# B105B.net
KiCad netlist of a schematic drawn in EAGLE
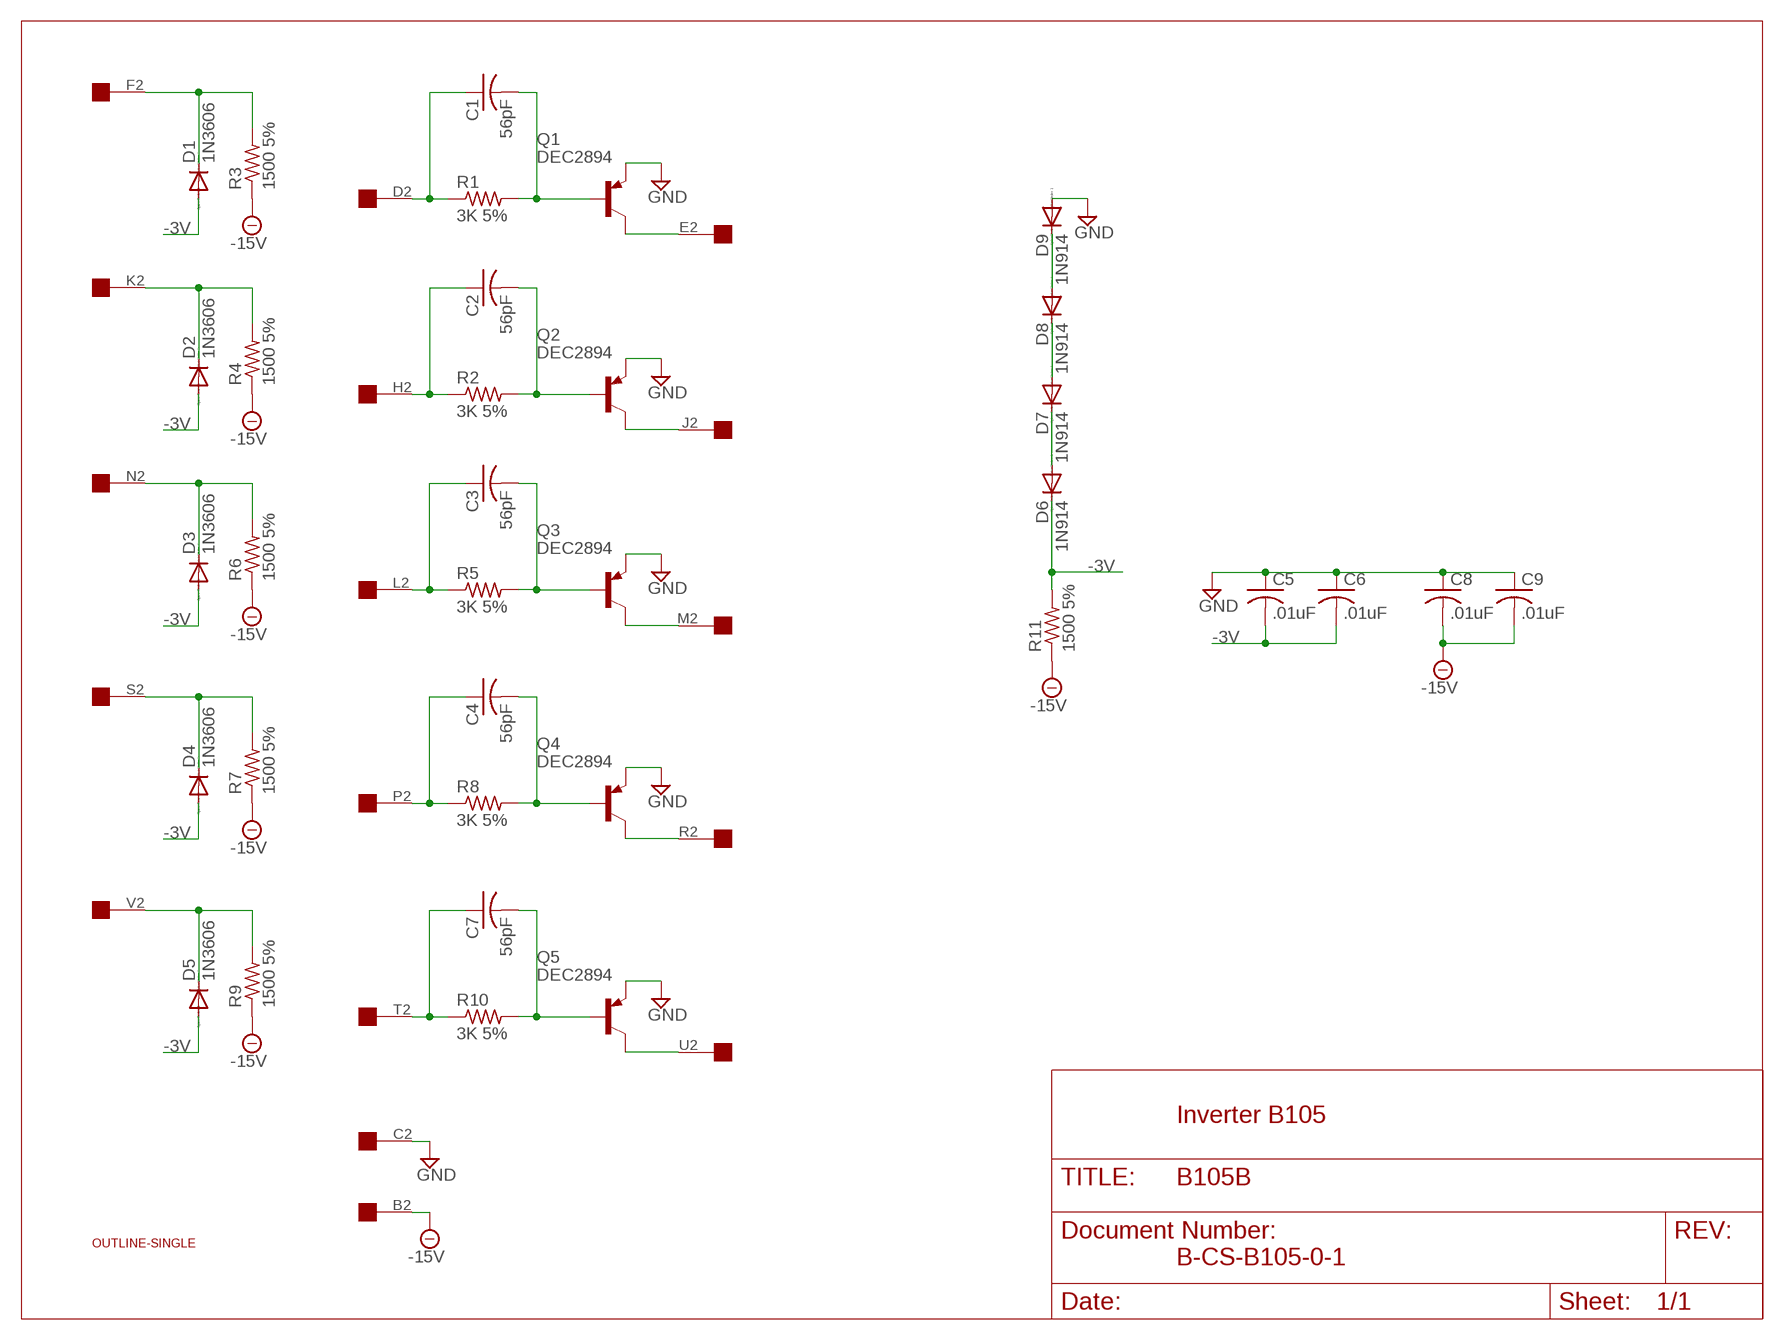
[diagram p0: schematic, sheet 1]

(export (version "E")
  (design (tool "Eeschema 10.0.6"))
  (components
    (comp (ref "C1")
      (value "56pF")
      (footprint "eagle-import:C075-032X103")
      (libsource (lib "eagle-import") (part "C-US075-032X103"))
    )
    (comp (ref "C2")
      (value "56pF")
      (footprint "eagle-import:C075-032X103")
      (libsource (lib "eagle-import") (part "C-US075-032X103"))
    )
    (comp (ref "C3")
      (value "56pF")
      (footprint "eagle-import:C075-032X103")
      (libsource (lib "eagle-import") (part "C-US075-032X103"))
    )
    (comp (ref "C4")
      (value "56pF")
      (footprint "eagle-import:C075-032X103")
      (libsource (lib "eagle-import") (part "C-US075-032X103"))
    )
    (comp (ref "C5")
      (value ".01uF")
      (footprint "eagle-import:C050-025X075")
      (libsource (lib "eagle-import") (part "C-US050-025X075"))
    )
    (comp (ref "C6")
      (value ".01uF")
      (footprint "eagle-import:C050-025X075")
      (libsource (lib "eagle-import") (part "C-US050-025X075"))
    )
    (comp (ref "C7")
      (value "56pF")
      (footprint "eagle-import:C075-032X103")
      (libsource (lib "eagle-import") (part "C-US075-032X103"))
    )
    (comp (ref "C8")
      (value ".01uF")
      (footprint "eagle-import:C050-025X075")
      (libsource (lib "eagle-import") (part "C-US050-025X075"))
    )
    (comp (ref "C9")
      (value ".01uF")
      (footprint "eagle-import:C050-025X075")
      (libsource (lib "eagle-import") (part "C-US050-025X075"))
    )
    (comp (ref "D1")
      (value "1N3606")
      (footprint "eagle-import:DO35-10")
      (libsource (lib "eagle-import") (part "1N4148DO35-10"))
    )
    (comp (ref "D2")
      (value "1N3606")
      (footprint "eagle-import:DO35-10")
      (libsource (lib "eagle-import") (part "1N4148DO35-10"))
    )
    (comp (ref "D3")
      (value "1N3606")
      (footprint "eagle-import:DO35-10")
      (libsource (lib "eagle-import") (part "1N4148DO35-10"))
    )
    (comp (ref "D4")
      (value "1N3606")
      (footprint "eagle-import:DO35-10")
      (libsource (lib "eagle-import") (part "1N4148DO35-10"))
    )
    (comp (ref "D5")
      (value "1N3606")
      (footprint "eagle-import:DO35-10")
      (libsource (lib "eagle-import") (part "1N4148DO35-10"))
    )
    (comp (ref "D6")
      (value "1N914")
      (footprint "eagle-import:DO35-10")
      (libsource (lib "eagle-import") (part "1N4148DO35-10"))
    )
    (comp (ref "D7")
      (value "1N914")
      (footprint "eagle-import:DO35-10")
      (libsource (lib "eagle-import") (part "1N4148DO35-10"))
    )
    (comp (ref "D8")
      (value "1N914")
      (footprint "eagle-import:DO35-10")
      (libsource (lib "eagle-import") (part "1N4148DO35-10"))
    )
    (comp (ref "D9")
      (value "1N914")
      (footprint "eagle-import:DO35-10")
      (libsource (lib "eagle-import") (part "1N4148DO35-10"))
    )
    (comp (ref "Q1")
      (value "DEC2894")
      (footprint "eagle-import:TO39")
      (libsource (lib "eagle-import") (part "2N2904"))
    )
    (comp (ref "Q2")
      (value "DEC2894")
      (footprint "eagle-import:TO39")
      (libsource (lib "eagle-import") (part "2N2904"))
    )
    (comp (ref "Q3")
      (value "DEC2894")
      (footprint "eagle-import:TO39")
      (libsource (lib "eagle-import") (part "2N2904"))
    )
    (comp (ref "Q4")
      (value "DEC2894")
      (footprint "eagle-import:TO39")
      (libsource (lib "eagle-import") (part "2N2904"))
    )
    (comp (ref "Q5")
      (value "DEC2894")
      (footprint "eagle-import:TO39")
      (libsource (lib "eagle-import") (part "2N2904"))
    )
    (comp (ref "R1")
      (value "3K 5%")
      (footprint "eagle-import:0207_10")
      (libsource (lib "eagle-import") (part "R-US_0207/10"))
    )
    (comp (ref "R2")
      (value "3K 5%")
      (footprint "eagle-import:0207_10")
      (libsource (lib "eagle-import") (part "R-US_0207/10"))
    )
    (comp (ref "R3")
      (value "1500 5%")
      (footprint "eagle-import:0207_10")
      (libsource (lib "eagle-import") (part "R-US_0207/10"))
    )
    (comp (ref "R4")
      (value "1500 5%")
      (footprint "eagle-import:0207_10")
      (libsource (lib "eagle-import") (part "R-US_0207/10"))
    )
    (comp (ref "R5")
      (value "3K 5%")
      (footprint "eagle-import:0207_10")
      (libsource (lib "eagle-import") (part "R-US_0207/10"))
    )
    (comp (ref "R6")
      (value "1500 5%")
      (footprint "eagle-import:0207_10")
      (libsource (lib "eagle-import") (part "R-US_0207/10"))
    )
    (comp (ref "R7")
      (value "1500 5%")
      (footprint "eagle-import:0207_10")
      (libsource (lib "eagle-import") (part "R-US_0207/10"))
    )
    (comp (ref "R8")
      (value "3K 5%")
      (footprint "eagle-import:0207_10")
      (libsource (lib "eagle-import") (part "R-US_0207/10"))
    )
    (comp (ref "R9")
      (value "1500 5%")
      (footprint "eagle-import:0207_10")
      (libsource (lib "eagle-import") (part "R-US_0207/10"))
    )
    (comp (ref "R10")
      (value "3K 5%")
      (footprint "eagle-import:0207_10")
      (libsource (lib "eagle-import") (part "R-US_0207/10"))
    )
    (comp (ref "R11")
      (value "1500 5%")
      (footprint "eagle-import:0207_10")
      (libsource (lib "eagle-import") (part "R-US_0207/10"))
    )
    (comp (ref "U$1")
      (value "OUTLINE-SINGLE")
      (footprint "eagle-import:SINGLE")
      (libsource (lib "eagle-import") (part "OUTLINE-SINGLE"))
    )
    (comp (ref "U$2")
      (value "EDGE-1")
      (footprint "eagle-import:EDGE-CON1")
      (libsource (lib "eagle-import") (part "EDGE-1"))
    )
  )
  (nets
    (net (code "1") (name "-15V") (class "Default")
      (node (ref "C8") (pin "2") (pinfunction "2_2") (pintype "passive"))
      (node (ref "C9") (pin "2") (pinfunction "2_2") (pintype "passive"))
      (node (ref "R11") (pin "1") (pinfunction "1_1") (pintype "passive"))
      (node (ref "R3") (pin "1") (pinfunction "1_1") (pintype "passive"))
      (node (ref "R4") (pin "1") (pinfunction "1_1") (pintype "passive"))
      (node (ref "R6") (pin "1") (pinfunction "1_1") (pintype "passive"))
      (node (ref "R7") (pin "1") (pinfunction "1_1") (pintype "passive"))
      (node (ref "R9") (pin "1") (pinfunction "1_1") (pintype "passive"))
      (node (ref "U$2") (pin "B2") (pinfunction "1_B2") (pintype "bidirectional"))
    )
    (net (code "2") (name "/-3V") (class "Default")
      (node (ref "C5") (pin "2") (pinfunction "2_2") (pintype "passive"))
      (node (ref "C6") (pin "2") (pinfunction "2_2") (pintype "passive"))
      (node (ref "D1") (pin "A") (pinfunction "A_A") (pintype "passive"))
      (node (ref "D2") (pin "A") (pinfunction "A_A") (pintype "passive"))
      (node (ref "D3") (pin "A") (pinfunction "A_A") (pintype "passive"))
      (node (ref "D4") (pin "A") (pinfunction "A_A") (pintype "passive"))
      (node (ref "D5") (pin "A") (pinfunction "A_A") (pintype "passive"))
      (node (ref "D6") (pin "C") (pinfunction "C_C") (pintype "passive"))
      (node (ref "R11") (pin "2") (pinfunction "2_2") (pintype "passive"))
    )
    (net (code "3") (name "GND") (class "Default")
      (node (ref "C5") (pin "1") (pinfunction "1_1") (pintype "passive"))
      (node (ref "C6") (pin "1") (pinfunction "1_1") (pintype "passive"))
      (node (ref "C8") (pin "1") (pinfunction "1_1") (pintype "passive"))
      (node (ref "C9") (pin "1") (pinfunction "1_1") (pintype "passive"))
      (node (ref "D9") (pin "A") (pinfunction "A_A") (pintype "passive"))
      (node (ref "Q1") (pin "1") (pinfunction "E_1") (pintype "passive"))
      (node (ref "Q2") (pin "1") (pinfunction "E_1") (pintype "passive"))
      (node (ref "Q3") (pin "1") (pinfunction "E_1") (pintype "passive"))
      (node (ref "Q4") (pin "1") (pinfunction "E_1") (pintype "passive"))
      (node (ref "Q5") (pin "1") (pinfunction "E_1") (pintype "passive"))
      (node (ref "U$2") (pin "C2") (pinfunction "1_C2") (pintype "bidirectional"))
    )
    (net (code "4") (name "Net-(D6-PadA)") (class "Default")
      (node (ref "D6") (pin "A") (pinfunction "A_A") (pintype "passive"))
      (node (ref "D7") (pin "C") (pinfunction "C_C") (pintype "passive"))
    )
    (net (code "5") (name "Net-(D7-PadA)") (class "Default")
      (node (ref "D7") (pin "A") (pinfunction "A_A") (pintype "passive"))
      (node (ref "D8") (pin "C") (pinfunction "C_C") (pintype "passive"))
    )
    (net (code "6") (name "Net-(D8-PadA)") (class "Default")
      (node (ref "D8") (pin "A") (pinfunction "A_A") (pintype "passive"))
      (node (ref "D9") (pin "C") (pinfunction "C_C") (pintype "passive"))
    )
    (net (code "7") (name "Net-(Q1-B)") (class "Default")
      (node (ref "C1") (pin "2") (pinfunction "2_2") (pintype "passive"))
      (node (ref "Q1") (pin "2") (pinfunction "B_2") (pintype "passive"))
      (node (ref "R1") (pin "2") (pinfunction "2_2") (pintype "passive"))
    )
    (net (code "8") (name "Net-(Q1-C)") (class "Default")
      (node (ref "Q1") (pin "3") (pinfunction "C_3") (pintype "passive"))
      (node (ref "U$2") (pin "E2") (pinfunction "1_E2") (pintype "bidirectional"))
    )
    (net (code "9") (name "Net-(Q2-B)") (class "Default")
      (node (ref "C2") (pin "2") (pinfunction "2_2") (pintype "passive"))
      (node (ref "Q2") (pin "2") (pinfunction "B_2") (pintype "passive"))
      (node (ref "R2") (pin "2") (pinfunction "2_2") (pintype "passive"))
    )
    (net (code "10") (name "Net-(Q2-C)") (class "Default")
      (node (ref "Q2") (pin "3") (pinfunction "C_3") (pintype "passive"))
      (node (ref "U$2") (pin "J2") (pinfunction "1_J2") (pintype "bidirectional"))
    )
    (net (code "11") (name "Net-(Q3-B)") (class "Default")
      (node (ref "C3") (pin "2") (pinfunction "2_2") (pintype "passive"))
      (node (ref "Q3") (pin "2") (pinfunction "B_2") (pintype "passive"))
      (node (ref "R5") (pin "2") (pinfunction "2_2") (pintype "passive"))
    )
    (net (code "12") (name "Net-(Q3-C)") (class "Default")
      (node (ref "Q3") (pin "3") (pinfunction "C_3") (pintype "passive"))
      (node (ref "U$2") (pin "M2") (pinfunction "1_M2") (pintype "bidirectional"))
    )
    (net (code "13") (name "Net-(Q4-B)") (class "Default")
      (node (ref "C4") (pin "2") (pinfunction "2_2") (pintype "passive"))
      (node (ref "Q4") (pin "2") (pinfunction "B_2") (pintype "passive"))
      (node (ref "R8") (pin "2") (pinfunction "2_2") (pintype "passive"))
    )
    (net (code "14") (name "Net-(Q4-C)") (class "Default")
      (node (ref "Q4") (pin "3") (pinfunction "C_3") (pintype "passive"))
      (node (ref "U$2") (pin "R2") (pinfunction "1_R2") (pintype "bidirectional"))
    )
    (net (code "15") (name "Net-(Q5-B)") (class "Default")
      (node (ref "C7") (pin "2") (pinfunction "2_2") (pintype "passive"))
      (node (ref "Q5") (pin "2") (pinfunction "B_2") (pintype "passive"))
      (node (ref "R10") (pin "2") (pinfunction "2_2") (pintype "passive"))
    )
    (net (code "16") (name "Net-(Q5-C)") (class "Default")
      (node (ref "Q5") (pin "3") (pinfunction "C_3") (pintype "passive"))
      (node (ref "U$2") (pin "U2") (pinfunction "1_U2") (pintype "bidirectional"))
    )
    (net (code "17") (name "Net-(U$2D-1)") (class "Default")
      (node (ref "C1") (pin "1") (pinfunction "1_1") (pintype "passive"))
      (node (ref "R1") (pin "1") (pinfunction "1_1") (pintype "passive"))
      (node (ref "U$2") (pin "D2") (pinfunction "1_D2") (pintype "bidirectional"))
    )
    (net (code "18") (name "Net-(U$2F-1)") (class "Default")
      (node (ref "D1") (pin "C") (pinfunction "C_C") (pintype "passive"))
      (node (ref "R3") (pin "2") (pinfunction "2_2") (pintype "passive"))
      (node (ref "U$2") (pin "F2") (pinfunction "1_F2") (pintype "bidirectional"))
    )
    (net (code "19") (name "Net-(U$2G-1)") (class "Default")
      (node (ref "C2") (pin "1") (pinfunction "1_1") (pintype "passive"))
      (node (ref "R2") (pin "1") (pinfunction "1_1") (pintype "passive"))
      (node (ref "U$2") (pin "H2") (pinfunction "1_H2") (pintype "bidirectional"))
    )
    (net (code "20") (name "Net-(U$2I-1)") (class "Default")
      (node (ref "D2") (pin "C") (pinfunction "C_C") (pintype "passive"))
      (node (ref "R4") (pin "2") (pinfunction "2_2") (pintype "passive"))
      (node (ref "U$2") (pin "K2") (pinfunction "1_K2") (pintype "bidirectional"))
    )
    (net (code "21") (name "Net-(U$2J-1)") (class "Default")
      (node (ref "C3") (pin "1") (pinfunction "1_1") (pintype "passive"))
      (node (ref "R5") (pin "1") (pinfunction "1_1") (pintype "passive"))
      (node (ref "U$2") (pin "L2") (pinfunction "1_L2") (pintype "bidirectional"))
    )
    (net (code "22") (name "Net-(U$2L-1)") (class "Default")
      (node (ref "D3") (pin "C") (pinfunction "C_C") (pintype "passive"))
      (node (ref "R6") (pin "2") (pinfunction "2_2") (pintype "passive"))
      (node (ref "U$2") (pin "N2") (pinfunction "1_N2") (pintype "bidirectional"))
    )
    (net (code "23") (name "Net-(U$2M-1)") (class "Default")
      (node (ref "C4") (pin "1") (pinfunction "1_1") (pintype "passive"))
      (node (ref "R8") (pin "1") (pinfunction "1_1") (pintype "passive"))
      (node (ref "U$2") (pin "P2") (pinfunction "1_P2") (pintype "bidirectional"))
    )
    (net (code "24") (name "Net-(U$2O-1)") (class "Default")
      (node (ref "D4") (pin "C") (pinfunction "C_C") (pintype "passive"))
      (node (ref "R7") (pin "2") (pinfunction "2_2") (pintype "passive"))
      (node (ref "U$2") (pin "S2") (pinfunction "1_S2") (pintype "bidirectional"))
    )
    (net (code "25") (name "Net-(U$2P-1)") (class "Default")
      (node (ref "C7") (pin "1") (pinfunction "1_1") (pintype "passive"))
      (node (ref "R10") (pin "1") (pinfunction "1_1") (pintype "passive"))
      (node (ref "U$2") (pin "T2") (pinfunction "1_T2") (pintype "bidirectional"))
    )
    (net (code "26") (name "Net-(U$2R-1)") (class "Default")
      (node (ref "D5") (pin "C") (pinfunction "C_C") (pintype "passive"))
      (node (ref "R9") (pin "2") (pinfunction "2_2") (pintype "passive"))
      (node (ref "U$2") (pin "V2") (pinfunction "1_V2") (pintype "bidirectional"))
    )
  )
)
